# F28335.net
KiCad netlist of a schematic drawn in Altium Designer
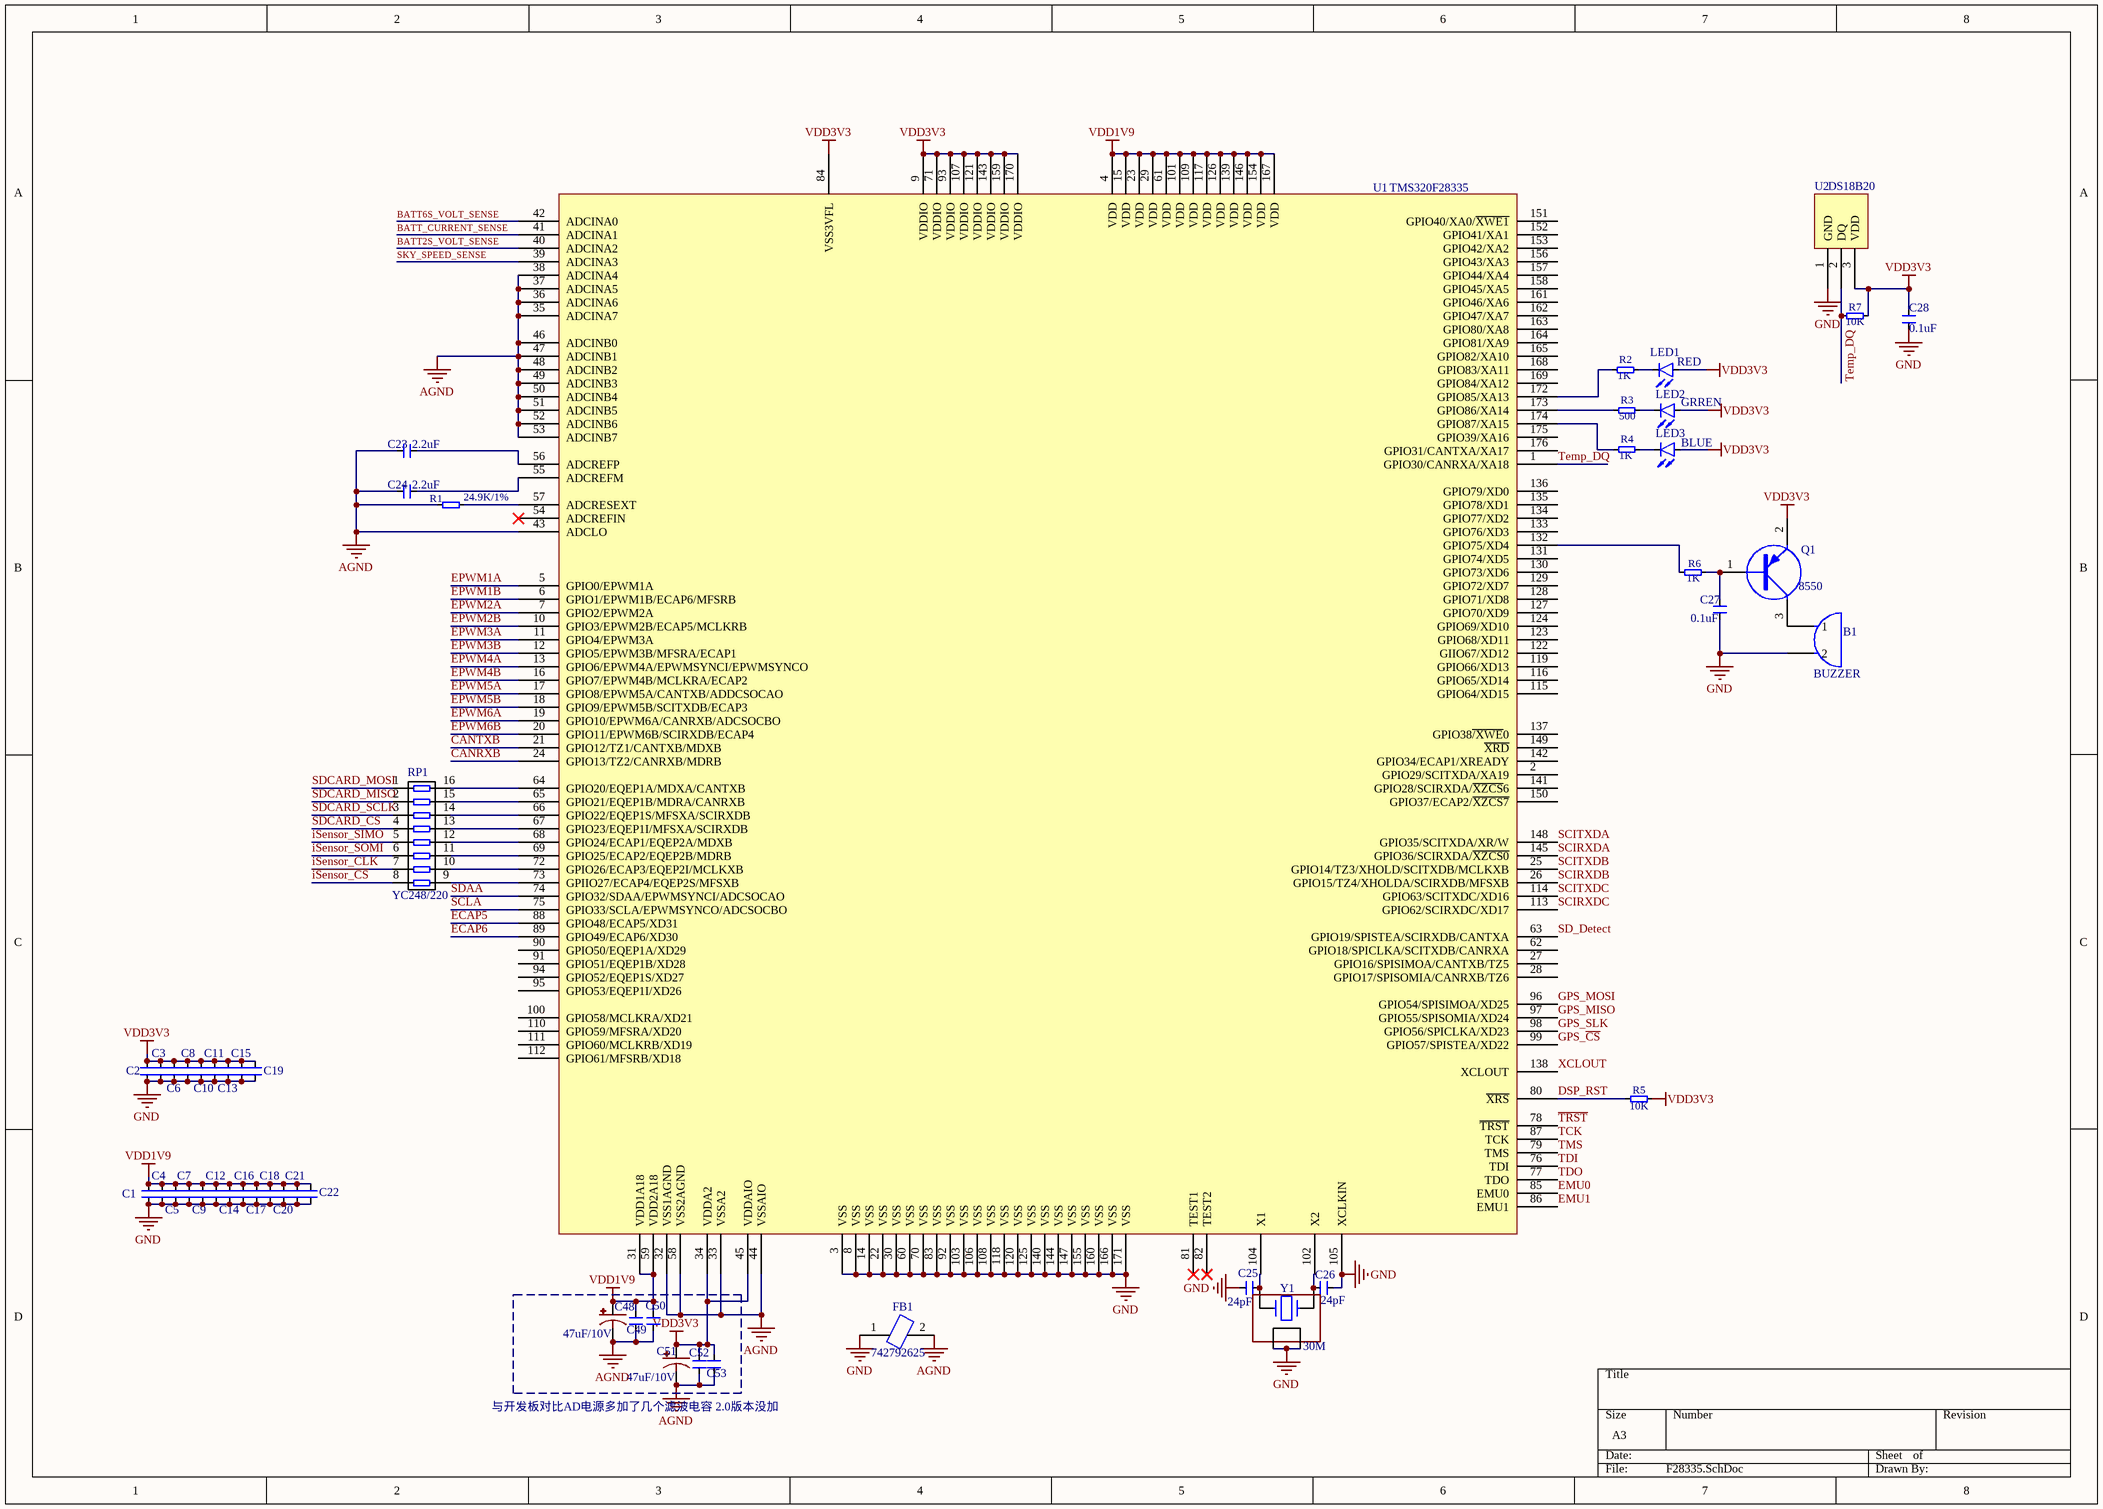
[diagram p0: F28335.SchDoc]

(export (version "E")
  (design (tool "Eeschema 10.0.6"))
  (components
    (comp (ref "B1")
      (value "BUZZER")
      (footprint "SMD-Beep(9.6*9.6)")
      (description "Buzzer")
      (libsource (lib "研发中心原理图库文件") (part "BUZZER"))
    )
    (comp (ref "C1") (value "0.1uF") (footprint "0603C") (libsource (lib "研发中心原理图库文件") (part "C")))
    (comp (ref "C2") (value "0.1uF") (footprint "0603C") (libsource (lib "研发中心原理图库文件") (part "C")))
    (comp (ref "C3") (value "0.1uF") (footprint "0603C") (libsource (lib "研发中心原理图库文件") (part "C")))
    (comp (ref "C4") (value "0.1uF") (footprint "0603C") (libsource (lib "研发中心原理图库文件") (part "C")))
    (comp (ref "C5") (value "0.1uF") (footprint "0603C") (libsource (lib "研发中心原理图库文件") (part "C")))
    (comp (ref "C6") (value "0.1uF") (footprint "0603C") (libsource (lib "研发中心原理图库文件") (part "C")))
    (comp (ref "C7") (value "0.1uF") (footprint "0603C") (libsource (lib "研发中心原理图库文件") (part "C")))
    (comp (ref "C8") (value "0.1uF") (footprint "0603C") (libsource (lib "研发中心原理图库文件") (part "C")))
    (comp (ref "C9") (value "0.1uF") (footprint "0603C") (libsource (lib "研发中心原理图库文件") (part "C")))
    (comp (ref "C10") (value "0.1uF") (footprint "0603C") (libsource (lib "研发中心原理图库文件") (part "C")))
    (comp (ref "C11") (value "0.1uF") (footprint "0603C") (libsource (lib "研发中心原理图库文件") (part "C")))
    (comp (ref "C12") (value "0.1uF") (footprint "0603C") (libsource (lib "研发中心原理图库文件") (part "C")))
    (comp (ref "C13") (value "0.1uF") (footprint "0603C") (libsource (lib "研发中心原理图库文件") (part "C")))
    (comp (ref "C14") (value "0.1uF") (footprint "0603C") (libsource (lib "研发中心原理图库文件") (part "C")))
    (comp (ref "C15") (value "0.1uF") (footprint "0603C") (libsource (lib "研发中心原理图库文件") (part "C")))
    (comp (ref "C16") (value "0.1uF") (footprint "0603C") (libsource (lib "研发中心原理图库文件") (part "C")))
    (comp (ref "C17") (value "0.1uF") (footprint "0603C") (libsource (lib "研发中心原理图库文件") (part "C")))
    (comp (ref "C18") (value "0.1uF") (footprint "0603C") (libsource (lib "研发中心原理图库文件") (part "C")))
    (comp (ref "C19") (value "0.1uF") (footprint "0603C") (libsource (lib "研发中心原理图库文件") (part "C")))
    (comp (ref "C20") (value "0.1uF") (footprint "0603C") (libsource (lib "研发中心原理图库文件") (part "C")))
    (comp (ref "C21") (value "0.1uF") (footprint "0603C") (libsource (lib "研发中心原理图库文件") (part "C")))
    (comp (ref "C22") (value "0.1uF") (footprint "0603C") (libsource (lib "研发中心原理图库文件") (part "C")))
    (comp (ref "C23") (value "2.2uF") (footprint "0603C") (libsource (lib "研发中心原理图库文件") (part "C")))
    (comp (ref "C24") (value "2.2uF") (footprint "0603C") (libsource (lib "研发中心原理图库文件") (part "C")))
    (comp (ref "C25") (value "24pF") (footprint "0603C") (libsource (lib "研发中心原理图库文件") (part "C")))
    (comp (ref "C26") (value "24pF") (footprint "0603C") (libsource (lib "研发中心原理图库文件") (part "C")))
    (comp (ref "C27") (value "0.1uF") (footprint "0603C") (libsource (lib "研发中心原理图库文件") (part "C")))
    (comp (ref "C28") (value "0.1uF") (footprint "0603C") (libsource (lib "研发中心原理图库文件") (part "C")))
    (comp (ref "C48") (value "47uF/10V") (footprint "3216/A") (libsource (lib "研发中心原理图库文件") (part "C-POLAR")))
    (comp (ref "C49") (value "0.1uF") (footprint "0603C") (libsource (lib "研发中心原理图库文件") (part "C")))
    (comp (ref "C50") (value "0.1uF") (footprint "0603C") (libsource (lib "研发中心原理图库文件") (part "C")))
    (comp (ref "C51") (value "47uF/10V") (footprint "3216/A") (libsource (lib "研发中心原理图库文件") (part "C-POLAR")))
    (comp (ref "C52") (value "0.1uF") (footprint "0603C") (libsource (lib "研发中心原理图库文件") (part "C")))
    (comp (ref "C53") (value "0.1uF") (footprint "0603C") (libsource (lib "研发中心原理图库文件") (part "C")))
    (comp (ref "FB1")
      (value "742792625")
      (footprint "研发中心PCB库文件:0603-FB")
      (libsource (lib "研发中心原理图库文件") (part "FB"))
    )
    (comp (ref "LED1") (value "RED") (footprint "0603D") (libsource (lib "研发中心原理图库文件") (part "LED")))
    (comp (ref "LED2") (value "GRREN") (footprint "0603D") (libsource (lib "研发中心原理图库文件") (part "LED")))
    (comp (ref "LED3") (value "BLUE") (footprint "0603D") (libsource (lib "研发中心原理图库文件") (part "LED")))
    (comp (ref "Q1")
      (value "8550")
      (footprint "SOT23-PNP")
      (description "PNP Transistor")
      (libsource (lib "研发中心原理图库文件") (part "PNP"))
    )
    (comp (ref "R1") (value "24.9K/1%") (footprint "0603R") (libsource (lib "研发中心原理图库文件") (part "R")))
    (comp (ref "R2") (value "1K") (footprint "0603R") (libsource (lib "研发中心原理图库文件") (part "R")))
    (comp (ref "R3") (value "500") (footprint "0603R") (libsource (lib "研发中心原理图库文件") (part "R")))
    (comp (ref "R4") (value "1K") (footprint "0603R") (libsource (lib "研发中心原理图库文件") (part "R")))
    (comp (ref "R5") (value "10K") (footprint "0603R") (libsource (lib "研发中心原理图库文件") (part "R")))
    (comp (ref "R6") (value "1K") (footprint "0603R") (libsource (lib "研发中心原理图库文件") (part "R")))
    (comp (ref "R7") (value "10K") (footprint "0603R") (libsource (lib "研发中心原理图库文件") (part "R")))
    (comp (ref "RP1")
      (value "YC248/220")
      (footprint "研发中心PCB库文件:YC248(0603x8)")
      (libsource (lib "研发中心原理图库文件") (part "RP"))
    )
    (comp (ref "U1")
      (value "TMS320F28335")
      (footprint "研发中心PCB库文件:LQFP-176")
      (libsource (lib "研发中心原理图库文件") (part "TMS320F28335"))
    )
    (comp (ref "U2") (value "DS18B20") (footprint "TO-92") (libsource (lib "研发中心原理图库文件") (part "DS18B20")))
    (comp (ref "Y1") (value "30M") (footprint "5032Y") (libsource (lib "研发中心原理图库文件") (part "Crystal-4")))
  )
  (nets
    (net (code "1") (name "/BATT2S_VOLT_SENSE") (class "Default")
      (node (ref "U1") (pin "40") (pinfunction "ADCINA2_40") (pintype "passive"))
    )
    (net (code "2") (name "/BATT6S_VOLT_SENSE") (class "Default")
      (node (ref "U1") (pin "42") (pinfunction "ADCINA0_42") (pintype "passive"))
    )
    (net (code "3") (name "/BATT_CURRENT_SENSE") (class "Default")
      (node (ref "U1") (pin "41") (pinfunction "ADCINA1_41") (pintype "passive"))
    )
    (net (code "4") (name "/CANRXB") (class "Default")
      (node (ref "U1") (pin "24") (pinfunction "GPIO13/TZ2/CANRXB/MDRB_24") (pintype "passive"))
    )
    (net (code "5") (name "/CANTXB") (class "Default")
      (node (ref "U1") (pin "21") (pinfunction "GPIO12/TZ1/CANTXB/MDXB_21") (pintype "passive"))
    )
    (net (code "6") (name "/DSP_RST") (class "Default")
      (node (ref "R5") (pin "1") (pintype "passive"))
      (node (ref "U1") (pin "80") (pinfunction "~{XRS}_80") (pintype "passive"))
    )
    (net (code "7") (name "/ECAP5") (class "Default")
      (node (ref "U1") (pin "88") (pinfunction "GPIO48/ECAP5/XD31_88") (pintype "passive"))
    )
    (net (code "8") (name "/ECAP6") (class "Default")
      (node (ref "U1") (pin "89") (pinfunction "GPIO49/ECAP6/XD30_89") (pintype "passive"))
    )
    (net (code "9") (name "/EMU0") (class "Default")
      (node (ref "U1") (pin "85") (pinfunction "EMU0_85") (pintype "passive"))
    )
    (net (code "10") (name "/EMU1") (class "Default")
      (node (ref "U1") (pin "86") (pinfunction "EMU1_86") (pintype "passive"))
    )
    (net (code "11") (name "/EPWM1A") (class "Default")
      (node (ref "U1") (pin "5") (pinfunction "GPIO0/EPWM1A_5") (pintype "passive"))
    )
    (net (code "12") (name "/EPWM1B") (class "Default")
      (node (ref "U1") (pin "6") (pinfunction "GPIO1/EPWM1B/ECAP6/MFSRB_6") (pintype "passive"))
    )
    (net (code "13") (name "/EPWM2A") (class "Default")
      (node (ref "U1") (pin "7") (pinfunction "GPIO2/EPWM2A_7") (pintype "passive"))
    )
    (net (code "14") (name "/EPWM2B") (class "Default")
      (node (ref "U1") (pin "10") (pinfunction "GPIO3/EPWM2B/ECAP5/MCLKRB_10") (pintype "passive"))
    )
    (net (code "15") (name "/EPWM3A") (class "Default")
      (node (ref "U1") (pin "11") (pinfunction "GPIO4/EPWM3A_11") (pintype "passive"))
    )
    (net (code "16") (name "/EPWM3B") (class "Default")
      (node (ref "U1") (pin "12") (pinfunction "GPIO5/EPWM3B/MFSRA/ECAP1_12") (pintype "passive"))
    )
    (net (code "17") (name "/EPWM4A") (class "Default")
      (node (ref "U1") (pin "13") (pinfunction "GPIO6/EPWM4A/EPWMSYNCI/EPWMSYNCO_13") (pintype "passive"))
    )
    (net (code "18") (name "/EPWM4B") (class "Default")
      (node (ref "U1") (pin "16") (pinfunction "GPIO7/EPWM4B/MCLKRA/ECAP2_16") (pintype "passive"))
    )
    (net (code "19") (name "/EPWM5A") (class "Default")
      (node (ref "U1") (pin "17") (pinfunction "GPIO8/EPWM5A/CANTXB/ADDCSOCAO_17") (pintype "passive"))
    )
    (net (code "20") (name "/EPWM5B") (class "Default")
      (node (ref "U1") (pin "18") (pinfunction "GPIO9/EPWM5B/SCITXDB/ECAP3_18") (pintype "passive"))
    )
    (net (code "21") (name "/EPWM6A") (class "Default")
      (node (ref "U1") (pin "19") (pinfunction "GPIO10/EPWM6A/CANRXB/ADCSOCBO_19") (pintype "passive"))
    )
    (net (code "22") (name "/EPWM6B") (class "Default")
      (node (ref "U1") (pin "20") (pinfunction "GPIO11/EPWM6B/SCIRXDB/ECAP4_20") (pintype "passive"))
    )
    (net (code "23") (name "/GPS_MISO") (class "Default")
      (node (ref "U1") (pin "97") (pinfunction "GPIO55/SPISOMIA/XD24_97") (pintype "passive"))
    )
    (net (code "24") (name "/GPS_MOSI") (class "Default")
      (node (ref "U1") (pin "96") (pinfunction "GPIO54/SPISIMOA/XD25_96") (pintype "passive"))
    )
    (net (code "25") (name "/GPS_SLK") (class "Default")
      (node (ref "U1") (pin "98") (pinfunction "GPIO56/SPICLKA/XD23_98") (pintype "passive"))
    )
    (net (code "26") (name "/GPS_~{CS}") (class "Default")
      (node (ref "U1") (pin "99") (pinfunction "GPIO57/SPISTEA/XD22_99") (pintype "passive"))
    )
    (net (code "27") (name "/SCIRXDA") (class "Default")
      (node (ref "U1") (pin "145") (pinfunction "GPIO36/SCIRXDA/~{XZCS0}_145") (pintype "passive"))
    )
    (net (code "28") (name "/SCIRXDB") (class "Default")
      (node (ref "U1") (pin "26") (pinfunction "GPIO15/TZ4/XHOLDA/SCIRXDB/MFSXB_26") (pintype "passive"))
    )
    (net (code "29") (name "/SCIRXDC") (class "Default")
      (node (ref "U1") (pin "113") (pinfunction "GPIO62/SCIRXDC/XD17_113") (pintype "passive"))
    )
    (net (code "30") (name "/SCITXDA") (class "Default")
      (node (ref "U1") (pin "148") (pinfunction "GPIO35/SCITXDA/XR/W_148") (pintype "passive"))
    )
    (net (code "31") (name "/SCITXDB") (class "Default")
      (node (ref "U1") (pin "25") (pinfunction "GPIO14/TZ3/XHOLD/SCITXDB/MCLKXB_25") (pintype "passive"))
    )
    (net (code "32") (name "/SCITXDC") (class "Default")
      (node (ref "U1") (pin "114") (pinfunction "GPIO63/SCITXDC/XD16_114") (pintype "passive"))
    )
    (net (code "33") (name "/SCLA") (class "Default")
      (node (ref "U1") (pin "75") (pinfunction "GPIO33/SCLA/EPWMSYNCO/ADCSOCBO_75") (pintype "passive"))
    )
    (net (code "34") (name "/SDAA") (class "Default")
      (node (ref "U1") (pin "74") (pinfunction "GPIO32/SDAA/EPWMSYNCI/ADCSOCAO_74") (pintype "passive"))
    )
    (net (code "35") (name "/SDCARD_CS") (class "Default")
      (node (ref "RP1") (pin "4") (pinfunction "4_4") (pintype "passive"))
    )
    (net (code "36") (name "/SDCARD_MISO") (class "Default")
      (node (ref "RP1") (pin "2") (pinfunction "2_2") (pintype "passive"))
    )
    (net (code "37") (name "/SDCARD_MOSI") (class "Default")
      (node (ref "RP1") (pin "1") (pinfunction "1_1") (pintype "passive"))
    )
    (net (code "38") (name "/SDCARD_SCLK") (class "Default")
      (node (ref "RP1") (pin "3") (pinfunction "3_3") (pintype "passive"))
    )
    (net (code "39") (name "/SD_Detect") (class "Default")
      (node (ref "U1") (pin "63") (pinfunction "GPIO19/SPISTEA/SCIRXDB/CANTXA_63") (pintype "passive"))
    )
    (net (code "40") (name "/SKY_SPEED_SENSE") (class "Default")
      (node (ref "U1") (pin "39") (pinfunction "ADCINA3_39") (pintype "passive"))
    )
    (net (code "41") (name "/TCK") (class "Default")
      (node (ref "U1") (pin "87") (pinfunction "TCK_87") (pintype "passive"))
    )
    (net (code "42") (name "/TDI") (class "Default")
      (node (ref "U1") (pin "76") (pinfunction "TDI_76") (pintype "passive"))
    )
    (net (code "43") (name "/TDO") (class "Default")
      (node (ref "U1") (pin "77") (pinfunction "TDO_77") (pintype "passive"))
    )
    (net (code "44") (name "/TMS") (class "Default")
      (node (ref "U1") (pin "79") (pinfunction "TMS_79") (pintype "passive"))
    )
    (net (code "45") (name "/Temp_DQ") (class "Default")
      (node (ref "R7") (pin "2") (pintype "passive"))
      (node (ref "U1") (pin "1") (pinfunction "GPIO30/CANRXA/XA18_1") (pintype "passive"))
      (node (ref "U2") (pin "2") (pinfunction "DQ_2") (pintype "passive"))
    )
    (net (code "46") (name "/XCLOUT") (class "Default")
      (node (ref "U1") (pin "138") (pinfunction "XCLOUT_138") (pintype "passive"))
    )
    (net (code "47") (name "/iSensor_CLK") (class "Default")
      (node (ref "RP1") (pin "7") (pinfunction "7_7") (pintype "passive"))
    )
    (net (code "48") (name "/iSensor_SIMO") (class "Default")
      (node (ref "RP1") (pin "5") (pinfunction "5_5") (pintype "passive"))
    )
    (net (code "49") (name "/iSensor_SOMI") (class "Default")
      (node (ref "RP1") (pin "6") (pinfunction "6_6") (pintype "passive"))
    )
    (net (code "50") (name "/~{TRST}") (class "Default")
      (node (ref "U1") (pin "78") (pinfunction "~{TRST}_78") (pintype "passive"))
    )
    (net (code "51") (name "/~{iSensor_CS}") (class "Default")
      (node (ref "RP1") (pin "8") (pinfunction "8_8") (pintype "passive"))
    )
    (net (code "52") (name "AGND") (class "Default")
      (node (ref "C23") (pin "2") (pintype "passive"))
      (node (ref "C24") (pin "2") (pintype "passive"))
      (node (ref "C48") (pin "2") (pinfunction "2_2") (pintype "passive"))
      (node (ref "C49") (pin "2") (pintype "passive"))
      (node (ref "C50") (pin "2") (pintype "passive"))
      (node (ref "C51") (pin "2") (pinfunction "2_2") (pintype "passive"))
      (node (ref "C52") (pin "2") (pintype "passive"))
      (node (ref "C53") (pin "2") (pintype "passive"))
      (node (ref "FB1") (pin "2") (pinfunction "2_2") (pintype "passive"))
      (node (ref "R1") (pin "1") (pintype "passive"))
      (node (ref "U1") (pin "32") (pinfunction "VSS1AGND_32") (pintype "passive"))
      (node (ref "U1") (pin "33") (pinfunction "VSSA2_33") (pintype "passive"))
      (node (ref "U1") (pin "35") (pinfunction "ADCINA7_35") (pintype "passive"))
      (node (ref "U1") (pin "36") (pinfunction "ADCINA6_36") (pintype "passive"))
      (node (ref "U1") (pin "37") (pinfunction "ADCINA5_37") (pintype "passive"))
      (node (ref "U1") (pin "38") (pinfunction "ADCINA4_38") (pintype "passive"))
      (node (ref "U1") (pin "43") (pinfunction "ADCLO_43") (pintype "passive"))
      (node (ref "U1") (pin "44") (pinfunction "VSSAIO_44") (pintype "passive"))
      (node (ref "U1") (pin "46") (pinfunction "ADCINB0_46") (pintype "passive"))
      (node (ref "U1") (pin "47") (pinfunction "ADCINB1_47") (pintype "passive"))
      (node (ref "U1") (pin "48") (pinfunction "ADCINB2_48") (pintype "passive"))
      (node (ref "U1") (pin "49") (pinfunction "ADCINB3_49") (pintype "passive"))
      (node (ref "U1") (pin "50") (pinfunction "ADCINB4_50") (pintype "passive"))
      (node (ref "U1") (pin "51") (pinfunction "ADCINB5_51") (pintype "passive"))
      (node (ref "U1") (pin "52") (pinfunction "ADCINB6_52") (pintype "passive"))
      (node (ref "U1") (pin "53") (pinfunction "ADCINB7_53") (pintype "passive"))
      (node (ref "U1") (pin "58") (pinfunction "VSS2AGND_58") (pintype "passive"))
    )
    (net (code "53") (name "GND") (class "Default")
      (node (ref "B1") (pin "2") (pinfunction "2_2") (pintype "passive"))
      (node (ref "C1") (pin "2") (pintype "passive"))
      (node (ref "C10") (pin "2") (pintype "passive"))
      (node (ref "C11") (pin "2") (pintype "passive"))
      (node (ref "C12") (pin "2") (pintype "passive"))
      (node (ref "C13") (pin "2") (pintype "passive"))
      (node (ref "C14") (pin "2") (pintype "passive"))
      (node (ref "C15") (pin "2") (pintype "passive"))
      (node (ref "C16") (pin "2") (pintype "passive"))
      (node (ref "C17") (pin "2") (pintype "passive"))
      (node (ref "C18") (pin "2") (pintype "passive"))
      (node (ref "C19") (pin "2") (pintype "passive"))
      (node (ref "C2") (pin "2") (pintype "passive"))
      (node (ref "C20") (pin "2") (pintype "passive"))
      (node (ref "C21") (pin "2") (pintype "passive"))
      (node (ref "C22") (pin "2") (pintype "passive"))
      (node (ref "C25") (pin "2") (pintype "passive"))
      (node (ref "C26") (pin "1") (pintype "passive"))
      (node (ref "C27") (pin "1") (pintype "passive"))
      (node (ref "C28") (pin "1") (pintype "passive"))
      (node (ref "C3") (pin "2") (pintype "passive"))
      (node (ref "C4") (pin "2") (pintype "passive"))
      (node (ref "C5") (pin "2") (pintype "passive"))
      (node (ref "C6") (pin "2") (pintype "passive"))
      (node (ref "C7") (pin "2") (pintype "passive"))
      (node (ref "C8") (pin "2") (pintype "passive"))
      (node (ref "C9") (pin "2") (pintype "passive"))
      (node (ref "FB1") (pin "1") (pinfunction "1_1") (pintype "passive"))
      (node (ref "U1") (pin "103") (pinfunction "VSS_103") (pintype "passive"))
      (node (ref "U1") (pin "105") (pinfunction "XCLKIN_105") (pintype "passive"))
      (node (ref "U1") (pin "106") (pinfunction "VSS_106") (pintype "passive"))
      (node (ref "U1") (pin "108") (pinfunction "VSS_108") (pintype "passive"))
      (node (ref "U1") (pin "118") (pinfunction "VSS_118") (pintype "passive"))
      (node (ref "U1") (pin "120") (pinfunction "VSS_120") (pintype "passive"))
      (node (ref "U1") (pin "125") (pinfunction "VSS_125") (pintype "passive"))
      (node (ref "U1") (pin "14") (pinfunction "VSS_14") (pintype "passive"))
      (node (ref "U1") (pin "140") (pinfunction "VSS_140") (pintype "passive"))
      (node (ref "U1") (pin "144") (pinfunction "VSS_144") (pintype "passive"))
      (node (ref "U1") (pin "147") (pinfunction "VSS_147") (pintype "passive"))
      (node (ref "U1") (pin "155") (pinfunction "VSS_155") (pintype "passive"))
      (node (ref "U1") (pin "160") (pinfunction "VSS_160") (pintype "passive"))
      (node (ref "U1") (pin "166") (pinfunction "VSS_166") (pintype "passive"))
      (node (ref "U1") (pin "171") (pinfunction "VSS_171") (pintype "passive"))
      (node (ref "U1") (pin "22") (pinfunction "VSS_22") (pintype "passive"))
      (node (ref "U1") (pin "3") (pinfunction "VSS_3") (pintype "passive"))
      (node (ref "U1") (pin "30") (pinfunction "VSS_30") (pintype "passive"))
      (node (ref "U1") (pin "60") (pinfunction "VSS_60") (pintype "passive"))
      (node (ref "U1") (pin "70") (pinfunction "VSS_70") (pintype "passive"))
      (node (ref "U1") (pin "8") (pinfunction "VSS_8") (pintype "passive"))
      (node (ref "U1") (pin "83") (pinfunction "VSS_83") (pintype "passive"))
      (node (ref "U1") (pin "92") (pinfunction "VSS_92") (pintype "passive"))
      (node (ref "U2") (pin "1") (pinfunction "GND_1") (pintype "passive"))
      (node (ref "Y1") (pin "2") (pinfunction "2_2") (pintype "passive"))
      (node (ref "Y1") (pin "4") (pinfunction "4_4") (pintype "passive"))
    )
    (net (code "54") (name "Net-(LED1-Pad2)") (class "Default")
      (node (ref "LED1") (pin "2") (pinfunction "2_2") (pintype "passive"))
      (node (ref "R2") (pin "2") (pintype "passive"))
    )
    (net (code "55") (name "Net-(LED2-Pad2)") (class "Default")
      (node (ref "LED2") (pin "2") (pinfunction "2_2") (pintype "passive"))
      (node (ref "R3") (pin "2") (pintype "passive"))
    )
    (net (code "56") (name "Net-(LED3-Pad2)") (class "Default")
      (node (ref "LED3") (pin "2") (pinfunction "2_2") (pintype "passive"))
      (node (ref "R4") (pin "2") (pintype "passive"))
    )
    (net (code "57") (name "Net-(Q1-B)") (class "Default")
      (node (ref "C27") (pin "2") (pintype "passive"))
      (node (ref "Q1") (pin "1") (pinfunction "B_1") (pintype "passive"))
      (node (ref "R6") (pin "2") (pintype "passive"))
    )
    (net (code "58") (name "Net-(Q1-C)") (class "Default")
      (node (ref "B1") (pin "1") (pinfunction "1_1") (pintype "passive"))
      (node (ref "Q1") (pin "3") (pinfunction "C_3") (pintype "passive"))
    )
    (net (code "59") (name "Net-(U1-ADCREFM)") (class "Default")
      (node (ref "C24") (pin "1") (pintype "passive"))
      (node (ref "U1") (pin "55") (pinfunction "ADCREFM_55") (pintype "passive"))
    )
    (net (code "60") (name "Net-(U1-ADCREFP)") (class "Default")
      (node (ref "C23") (pin "1") (pintype "passive"))
      (node (ref "U1") (pin "56") (pinfunction "ADCREFP_56") (pintype "passive"))
    )
    (net (code "61") (name "Net-(U1-ADCRESEXT)") (class "Default")
      (node (ref "R1") (pin "2") (pintype "passive"))
      (node (ref "U1") (pin "57") (pinfunction "ADCRESEXT_57") (pintype "passive"))
    )
    (net (code "62") (name "Net-(U1-GPIIO27{slash}ECAP4{slash}EQEP2S{slash}MFSXB)") (class "Default")
      (node (ref "RP1") (pin "9") (pinfunction "9_9") (pintype "passive"))
      (node (ref "U1") (pin "73") (pinfunction "GPIIO27/ECAP4/EQEP2S/MFSXB_73") (pintype "passive"))
    )
    (net (code "63") (name "Net-(U1-GPIO20{slash}EQEP1A{slash}MDXA{slash}CANTXB)") (class "Default")
      (node (ref "RP1") (pin "16") (pinfunction "16_16") (pintype "passive"))
      (node (ref "U1") (pin "64") (pinfunction "GPIO20/EQEP1A/MDXA/CANTXB_64") (pintype "passive"))
    )
    (net (code "64") (name "Net-(U1-GPIO21{slash}EQEP1B{slash}MDRA{slash}CANRXB)") (class "Default")
      (node (ref "RP1") (pin "15") (pinfunction "15_15") (pintype "passive"))
      (node (ref "U1") (pin "65") (pinfunction "GPIO21/EQEP1B/MDRA/CANRXB_65") (pintype "passive"))
    )
    (net (code "65") (name "Net-(U1-GPIO22{slash}EQEP1S{slash}MFSXA{slash}SCIRXDB)") (class "Default")
      (node (ref "RP1") (pin "14") (pinfunction "14_14") (pintype "passive"))
      (node (ref "U1") (pin "66") (pinfunction "GPIO22/EQEP1S/MFSXA/SCIRXDB_66") (pintype "passive"))
    )
    (net (code "66") (name "Net-(U1-GPIO23{slash}EQEP1I{slash}MFSXA{slash}SCIRXDB)") (class "Default")
      (node (ref "RP1") (pin "13") (pinfunction "13_13") (pintype "passive"))
      (node (ref "U1") (pin "67") (pinfunction "GPIO23/EQEP1I/MFSXA/SCIRXDB_67") (pintype "passive"))
    )
    (net (code "67") (name "Net-(U1-GPIO24{slash}ECAP1{slash}EQEP2A{slash}MDXB)") (class "Default")
      (node (ref "RP1") (pin "12") (pinfunction "12_12") (pintype "passive"))
      (node (ref "U1") (pin "68") (pinfunction "GPIO24/ECAP1/EQEP2A/MDXB_68") (pintype "passive"))
    )
    (net (code "68") (name "Net-(U1-GPIO25{slash}ECAP2{slash}EQEP2B{slash}MDRB)") (class "Default")
      (node (ref "RP1") (pin "11") (pinfunction "11_11") (pintype "passive"))
      (node (ref "U1") (pin "69") (pinfunction "GPIO25/ECAP2/EQEP2B/MDRB_69") (pintype "passive"))
    )
    (net (code "69") (name "Net-(U1-GPIO26{slash}ECAP3{slash}EQEP2I{slash}MCLKXB)") (class "Default")
      (node (ref "RP1") (pin "10") (pinfunction "10_10") (pintype "passive"))
      (node (ref "U1") (pin "72") (pinfunction "GPIO26/ECAP3/EQEP2I/MCLKXB_72") (pintype "passive"))
    )
    (net (code "70") (name "Net-(U1-GPIO75{slash}XD4)") (class "Default")
      (node (ref "R6") (pin "1") (pintype "passive"))
      (node (ref "U1") (pin "132") (pinfunction "GPIO75/XD4_132") (pintype "passive"))
    )
    (net (code "71") (name "Net-(U1-GPIO85{slash}XA13)") (class "Default")
      (node (ref "R2") (pin "1") (pintype "passive"))
      (node (ref "U1") (pin "172") (pinfunction "GPIO85/XA13_172") (pintype "passive"))
    )
    (net (code "72") (name "Net-(U1-GPIO86{slash}XA14)") (class "Default")
      (node (ref "R3") (pin "1") (pintype "passive"))
      (node (ref "U1") (pin "173") (pinfunction "GPIO86/XA14_173") (pintype "passive"))
    )
    (net (code "73") (name "Net-(U1-GPIO87{slash}XA15)") (class "Default")
      (node (ref "R4") (pin "1") (pintype "passive"))
      (node (ref "U1") (pin "174") (pinfunction "GPIO87/XA15_174") (pintype "passive"))
    )
    (net (code "74") (name "Net-(U1-X1)") (class "Default")
      (node (ref "C25") (pin "1") (pintype "passive"))
      (node (ref "U1") (pin "104") (pinfunction "X1_104") (pintype "passive"))
      (node (ref "Y1") (pin "1") (pinfunction "1_1") (pintype "passive"))
    )
    (net (code "75") (name "Net-(U1-X2)") (class "Default")
      (node (ref "C26") (pin "2") (pintype "passive"))
      (node (ref "U1") (pin "102") (pinfunction "X2_102") (pintype "passive"))
      (node (ref "Y1") (pin "3") (pinfunction "3_3") (pintype "passive"))
    )
    (net (code "76") (name "VDD1V9") (class "Default")
      (node (ref "C1") (pin "1") (pintype "passive"))
      (node (ref "C12") (pin "1") (pintype "passive"))
      (node (ref "C14") (pin "1") (pintype "passive"))
      (node (ref "C16") (pin "1") (pintype "passive"))
      (node (ref "C17") (pin "1") (pintype "passive"))
      (node (ref "C18") (pin "1") (pintype "passive"))
      (node (ref "C20") (pin "1") (pintype "passive"))
      (node (ref "C21") (pin "1") (pintype "passive"))
      (node (ref "C22") (pin "1") (pintype "passive"))
      (node (ref "C4") (pin "1") (pintype "passive"))
      (node (ref "C48") (pin "1") (pinfunction "1_1") (pintype "passive"))
      (node (ref "C49") (pin "1") (pintype "passive"))
      (node (ref "C5") (pin "1") (pintype "passive"))
      (node (ref "C50") (pin "1") (pintype "passive"))
      (node (ref "C7") (pin "1") (pintype "passive"))
      (node (ref "C9") (pin "1") (pintype "passive"))
      (node (ref "U1") (pin "101") (pinfunction "VDD_101") (pintype "passive"))
      (node (ref "U1") (pin "109") (pinfunction "VDD_109") (pintype "passive"))
      (node (ref "U1") (pin "117") (pinfunction "VDD_117") (pintype "passive"))
      (node (ref "U1") (pin "126") (pinfunction "VDD_126") (pintype "passive"))
      (node (ref "U1") (pin "139") (pinfunction "VDD_139") (pintype "passive"))
      (node (ref "U1") (pin "146") (pinfunction "VDD_146") (pintype "passive"))
      (node (ref "U1") (pin "15") (pinfunction "VDD_15") (pintype "passive"))
      (node (ref "U1") (pin "154") (pinfunction "VDD_154") (pintype "passive"))
      (node (ref "U1") (pin "167") (pinfunction "VDD_167") (pintype "passive"))
      (node (ref "U1") (pin "23") (pinfunction "VDD_23") (pintype "passive"))
      (node (ref "U1") (pin "29") (pinfunction "VDD_29") (pintype "passive"))
      (node (ref "U1") (pin "31") (pinfunction "VDD1A18_31") (pintype "passive"))
      (node (ref "U1") (pin "4") (pinfunction "VDD_4") (pintype "passive"))
      (node (ref "U1") (pin "59") (pinfunction "VDD2A18_59") (pintype "passive"))
      (node (ref "U1") (pin "61") (pinfunction "VDD_61") (pintype "passive"))
    )
    (net (code "77") (name "VDD3V3") (class "Default")
      (node (ref "C10") (pin "1") (pintype "passive"))
      (node (ref "C11") (pin "1") (pintype "passive"))
      (node (ref "C13") (pin "1") (pintype "passive"))
      (node (ref "C15") (pin "1") (pintype "passive"))
      (node (ref "C19") (pin "1") (pintype "passive"))
      (node (ref "C2") (pin "1") (pintype "passive"))
      (node (ref "C28") (pin "2") (pintype "passive"))
      (node (ref "C3") (pin "1") (pintype "passive"))
      (node (ref "C51") (pin "1") (pinfunction "1_1") (pintype "passive"))
      (node (ref "C52") (pin "1") (pintype "passive"))
      (node (ref "C53") (pin "1") (pintype "passive"))
      (node (ref "C6") (pin "1") (pintype "passive"))
      (node (ref "C8") (pin "1") (pintype "passive"))
      (node (ref "LED1") (pin "1") (pinfunction "1_1") (pintype "passive"))
      (node (ref "LED2") (pin "1") (pinfunction "1_1") (pintype "passive"))
      (node (ref "LED3") (pin "1") (pinfunction "1_1") (pintype "passive"))
      (node (ref "Q1") (pin "2") (pinfunction "E_2") (pintype "passive"))
      (node (ref "R5") (pin "2") (pintype "passive"))
      (node (ref "R7") (pin "1") (pintype "passive"))
      (node (ref "U1") (pin "107") (pinfunction "VDDIO_107") (pintype "passive"))
      (node (ref "U1") (pin "121") (pinfunction "VDDIO_121") (pintype "passive"))
      (node (ref "U1") (pin "143") (pinfunction "VDDIO_143") (pintype "passive"))
      (node (ref "U1") (pin "159") (pinfunction "VDDIO_159") (pintype "passive"))
      (node (ref "U1") (pin "170") (pinfunction "VDDIO_170") (pintype "passive"))
      (node (ref "U1") (pin "34") (pinfunction "VDDA2_34") (pintype "passive"))
      (node (ref "U1") (pin "45") (pinfunction "VDDAIO_45") (pintype "passive"))
      (node (ref "U1") (pin "71") (pinfunction "VDDIO_71") (pintype "passive"))
      (node (ref "U1") (pin "84") (pinfunction "VSS3VFL_84") (pintype "passive"))
      (node (ref "U1") (pin "9") (pinfunction "VDDIO_9") (pintype "passive"))
      (node (ref "U1") (pin "93") (pinfunction "VDDIO_93") (pintype "passive"))
      (node (ref "U2") (pin "3") (pinfunction "VDD_3") (pintype "passive"))
    )
    (net (code "78") (name "unconnected-(U1-ADCREFIN-Pad54)") (class "Default")
      (node (ref "U1") (pin "54") (pinfunction "ADCREFIN_54") (pintype "passive+no_connect"))
    )
    (net (code "79") (name "unconnected-(U1-GIIO67{slash}XD12-Pad122)") (class "Default")
      (node (ref "U1") (pin "122") (pinfunction "GIIO67/XD12_122") (pintype "passive"))
    )
    (net (code "80") (name "unconnected-(U1-GPIO16{slash}SPISIMOA{slash}CANTXB{slash}TZ5-Pad27)") (class "Default")
      (node (ref "U1") (pin "27") (pinfunction "GPIO16/SPISIMOA/CANTXB/TZ5_27") (pintype "passive"))
    )
    (net (code "81") (name "unconnected-(U1-GPIO17{slash}SPISOMIA{slash}CANRXB{slash}TZ6-Pad28)") (class "Default")
      (node (ref "U1") (pin "28") (pinfunction "GPIO17/SPISOMIA/CANRXB/TZ6_28") (pintype "passive"))
    )
    (net (code "82") (name "unconnected-(U1-GPIO18{slash}SPICLKA{slash}SCITXDB{slash}CANRXA-Pad62)") (class "Default")
      (node (ref "U1") (pin "62") (pinfunction "GPIO18/SPICLKA/SCITXDB/CANRXA_62") (pintype "passive"))
    )
    (net (code "83") (name "unconnected-(U1-GPIO28{slash}SCIRXDA{slash}~{XZCS}6-Pad141)") (class "Default")
      (node (ref "U1") (pin "141") (pinfunction "GPIO28/SCIRXDA/~{XZCS}6_141") (pintype "passive"))
    )
    (net (code "84") (name "unconnected-(U1-GPIO29{slash}SCITXDA{slash}XA19-Pad2)") (class "Default")
      (node (ref "U1") (pin "2") (pinfunction "GPIO29/SCITXDA/XA19_2") (pintype "passive"))
    )
    (net (code "85") (name "unconnected-(U1-GPIO31{slash}CANTXA{slash}XA17-Pad176)") (class "Default")
      (node (ref "U1") (pin "176") (pinfunction "GPIO31/CANTXA/XA17_176") (pintype "passive"))
    )
    (net (code "86") (name "unconnected-(U1-GPIO34{slash}ECAP1{slash}XREADY-Pad142)") (class "Default")
      (node (ref "U1") (pin "142") (pinfunction "GPIO34/ECAP1/XREADY_142") (pintype "passive"))
    )
    (net (code "87") (name "unconnected-(U1-GPIO37{slash}ECAP2{slash}~{XZCS7}-Pad150)") (class "Default")
      (node (ref "U1") (pin "150") (pinfunction "GPIO37/ECAP2/~{XZCS7}_150") (pintype "passive"))
    )
    (net (code "88") (name "unconnected-(U1-GPIO38~{{slash}XWE}0-Pad137)") (class "Default")
      (node (ref "U1") (pin "137") (pinfunction "GPIO38~{/XWE}0_137") (pintype "passive"))
    )
    (net (code "89") (name "unconnected-(U1-GPIO39{slash}XA16-Pad175)") (class "Default")
      (node (ref "U1") (pin "175") (pinfunction "GPIO39/XA16_175") (pintype "passive"))
    )
    (net (code "90") (name "unconnected-(U1-GPIO40{slash}XA0{slash}~{XWE1}-Pad151)") (class "Default")
      (node (ref "U1") (pin "151") (pinfunction "GPIO40/XA0/~{XWE1}_151") (pintype "passive"))
    )
    (net (code "91") (name "unconnected-(U1-GPIO41{slash}XA1-Pad152)") (class "Default")
      (node (ref "U1") (pin "152") (pinfunction "GPIO41/XA1_152") (pintype "passive"))
    )
    (net (code "92") (name "unconnected-(U1-GPIO42{slash}XA2-Pad153)") (class "Default")
      (node (ref "U1") (pin "153") (pinfunction "GPIO42/XA2_153") (pintype "passive"))
    )
    (net (code "93") (name "unconnected-(U1-GPIO43{slash}XA3-Pad156)") (class "Default")
      (node (ref "U1") (pin "156") (pinfunction "GPIO43/XA3_156") (pintype "passive"))
    )
    (net (code "94") (name "unconnected-(U1-GPIO44{slash}XA4-Pad157)") (class "Default")
      (node (ref "U1") (pin "157") (pinfunction "GPIO44/XA4_157") (pintype "passive"))
    )
    (net (code "95") (name "unconnected-(U1-GPIO45{slash}XA5-Pad158)") (class "Default")
      (node (ref "U1") (pin "158") (pinfunction "GPIO45/XA5_158") (pintype "passive"))
    )
    (net (code "96") (name "unconnected-(U1-GPIO46{slash}XA6-Pad161)") (class "Default")
      (node (ref "U1") (pin "161") (pinfunction "GPIO46/XA6_161") (pintype "passive"))
    )
    (net (code "97") (name "unconnected-(U1-GPIO47{slash}XA7-Pad162)") (class "Default")
      (node (ref "U1") (pin "162") (pinfunction "GPIO47/XA7_162") (pintype "passive"))
    )
    (net (code "98") (name "unconnected-(U1-GPIO50{slash}EQEP1A{slash}XD29-Pad90)") (class "Default")
      (node (ref "U1") (pin "90") (pinfunction "GPIO50/EQEP1A/XD29_90") (pintype "passive"))
    )
    (net (code "99") (name "unconnected-(U1-GPIO51{slash}EQEP1B{slash}XD28-Pad91)") (class "Default")
      (node (ref "U1") (pin "91") (pinfunction "GPIO51/EQEP1B/XD28_91") (pintype "passive"))
    )
    (net (code "100") (name "unconnected-(U1-GPIO52{slash}EQEP1S{slash}XD27-Pad94)") (class "Default")
      (node (ref "U1") (pin "94") (pinfunction "GPIO52/EQEP1S/XD27_94") (pintype "passive"))
    )
    (net (code "101") (name "unconnected-(U1-GPIO53{slash}EQEP1I{slash}XD26-Pad95)") (class "Default")
      (node (ref "U1") (pin "95") (pinfunction "GPIO53/EQEP1I/XD26_95") (pintype "passive"))
    )
    (net (code "102") (name "unconnected-(U1-GPIO58{slash}MCLKRA{slash}XD21-Pad100)") (class "Default")
      (node (ref "U1") (pin "100") (pinfunction "GPIO58/MCLKRA/XD21_100") (pintype "passive"))
    )
    (net (code "103") (name "unconnected-(U1-GPIO59{slash}MFSRA{slash}XD20-Pad110)") (class "Default")
      (node (ref "U1") (pin "110") (pinfunction "GPIO59/MFSRA/XD20_110") (pintype "passive"))
    )
    (net (code "104") (name "unconnected-(U1-GPIO60{slash}MCLKRB{slash}XD19-Pad111)") (class "Default")
      (node (ref "U1") (pin "111") (pinfunction "GPIO60/MCLKRB/XD19_111") (pintype "passive"))
    )
    (net (code "105") (name "unconnected-(U1-GPIO61{slash}MFSRB{slash}XD18-Pad112)") (class "Default")
      (node (ref "U1") (pin "112") (pinfunction "GPIO61/MFSRB/XD18_112") (pintype "passive"))
    )
    (net (code "106") (name "unconnected-(U1-GPIO64{slash}XD15-Pad115)") (class "Default")
      (node (ref "U1") (pin "115") (pinfunction "GPIO64/XD15_115") (pintype "passive"))
    )
    (net (code "107") (name "unconnected-(U1-GPIO65{slash}XD14-Pad116)") (class "Default")
      (node (ref "U1") (pin "116") (pinfunction "GPIO65/XD14_116") (pintype "passive"))
    )
    (net (code "108") (name "unconnected-(U1-GPIO66{slash}XD13-Pad119)") (class "Default")
      (node (ref "U1") (pin "119") (pinfunction "GPIO66/XD13_119") (pintype "passive"))
    )
    (net (code "109") (name "unconnected-(U1-GPIO68{slash}XD11-Pad123)") (class "Default")
      (node (ref "U1") (pin "123") (pinfunction "GPIO68/XD11_123") (pintype "passive"))
    )
    (net (code "110") (name "unconnected-(U1-GPIO69{slash}XD10-Pad124)") (class "Default")
      (node (ref "U1") (pin "124") (pinfunction "GPIO69/XD10_124") (pintype "passive"))
    )
    (net (code "111") (name "unconnected-(U1-GPIO70{slash}XD9-Pad127)") (class "Default")
      (node (ref "U1") (pin "127") (pinfunction "GPIO70/XD9_127") (pintype "passive"))
    )
    (net (code "112") (name "unconnected-(U1-GPIO71{slash}XD8-Pad128)") (class "Default")
      (node (ref "U1") (pin "128") (pinfunction "GPIO71/XD8_128") (pintype "passive"))
    )
    (net (code "113") (name "unconnected-(U1-GPIO72{slash}XD7-Pad129)") (class "Default")
      (node (ref "U1") (pin "129") (pinfunction "GPIO72/XD7_129") (pintype "passive"))
    )
    (net (code "114") (name "unconnected-(U1-GPIO73{slash}XD6-Pad130)") (class "Default")
      (node (ref "U1") (pin "130") (pinfunction "GPIO73/XD6_130") (pintype "passive"))
    )
    (net (code "115") (name "unconnected-(U1-GPIO74{slash}XD5-Pad131)") (class "Default")
      (node (ref "U1") (pin "131") (pinfunction "GPIO74/XD5_131") (pintype "passive"))
    )
    (net (code "116") (name "unconnected-(U1-GPIO76{slash}XD3-Pad133)") (class "Default")
      (node (ref "U1") (pin "133") (pinfunction "GPIO76/XD3_133") (pintype "passive"))
    )
    (net (code "117") (name "unconnected-(U1-GPIO77{slash}XD2-Pad134)") (class "Default")
      (node (ref "U1") (pin "134") (pinfunction "GPIO77/XD2_134") (pintype "passive"))
    )
    (net (code "118") (name "unconnected-(U1-GPIO78{slash}XD1-Pad135)") (class "Default")
      (node (ref "U1") (pin "135") (pinfunction "GPIO78/XD1_135") (pintype "passive"))
    )
    (net (code "119") (name "unconnected-(U1-GPIO79{slash}XD0-Pad136)") (class "Default")
      (node (ref "U1") (pin "136") (pinfunction "GPIO79/XD0_136") (pintype "passive"))
    )
    (net (code "120") (name "unconnected-(U1-GPIO80{slash}XA8-Pad163)") (class "Default")
      (node (ref "U1") (pin "163") (pinfunction "GPIO80/XA8_163") (pintype "passive"))
    )
    (net (code "121") (name "unconnected-(U1-GPIO81{slash}XA9-Pad164)") (class "Default")
      (node (ref "U1") (pin "164") (pinfunction "GPIO81/XA9_164") (pintype "passive"))
    )
    (net (code "122") (name "unconnected-(U1-GPIO82{slash}XA10-Pad165)") (class "Default")
      (node (ref "U1") (pin "165") (pinfunction "GPIO82/XA10_165") (pintype "passive"))
    )
    (net (code "123") (name "unconnected-(U1-GPIO83{slash}XA11-Pad168)") (class "Default")
      (node (ref "U1") (pin "168") (pinfunction "GPIO83/XA11_168") (pintype "passive"))
    )
    (net (code "124") (name "unconnected-(U1-GPIO84{slash}XA12-Pad169)") (class "Default")
      (node (ref "U1") (pin "169") (pinfunction "GPIO84/XA12_169") (pintype "passive"))
    )
    (net (code "125") (name "unconnected-(U1-TEST1-Pad81)") (class "Default")
      (node (ref "U1") (pin "81") (pinfunction "TEST1_81") (pintype "passive+no_connect"))
    )
    (net (code "126") (name "unconnected-(U1-TEST2-Pad82)") (class "Default")
      (node (ref "U1") (pin "82") (pinfunction "TEST2_82") (pintype "passive+no_connect"))
    )
    (net (code "127") (name "unconnected-(U1-~{XRD}-Pad149)") (class "Default")
      (node (ref "U1") (pin "149") (pinfunction "~{XRD}_149") (pintype "passive"))
    )
  )
)
